# esp32.net
KiCad netlist of a schematic drawn in Altium Designer
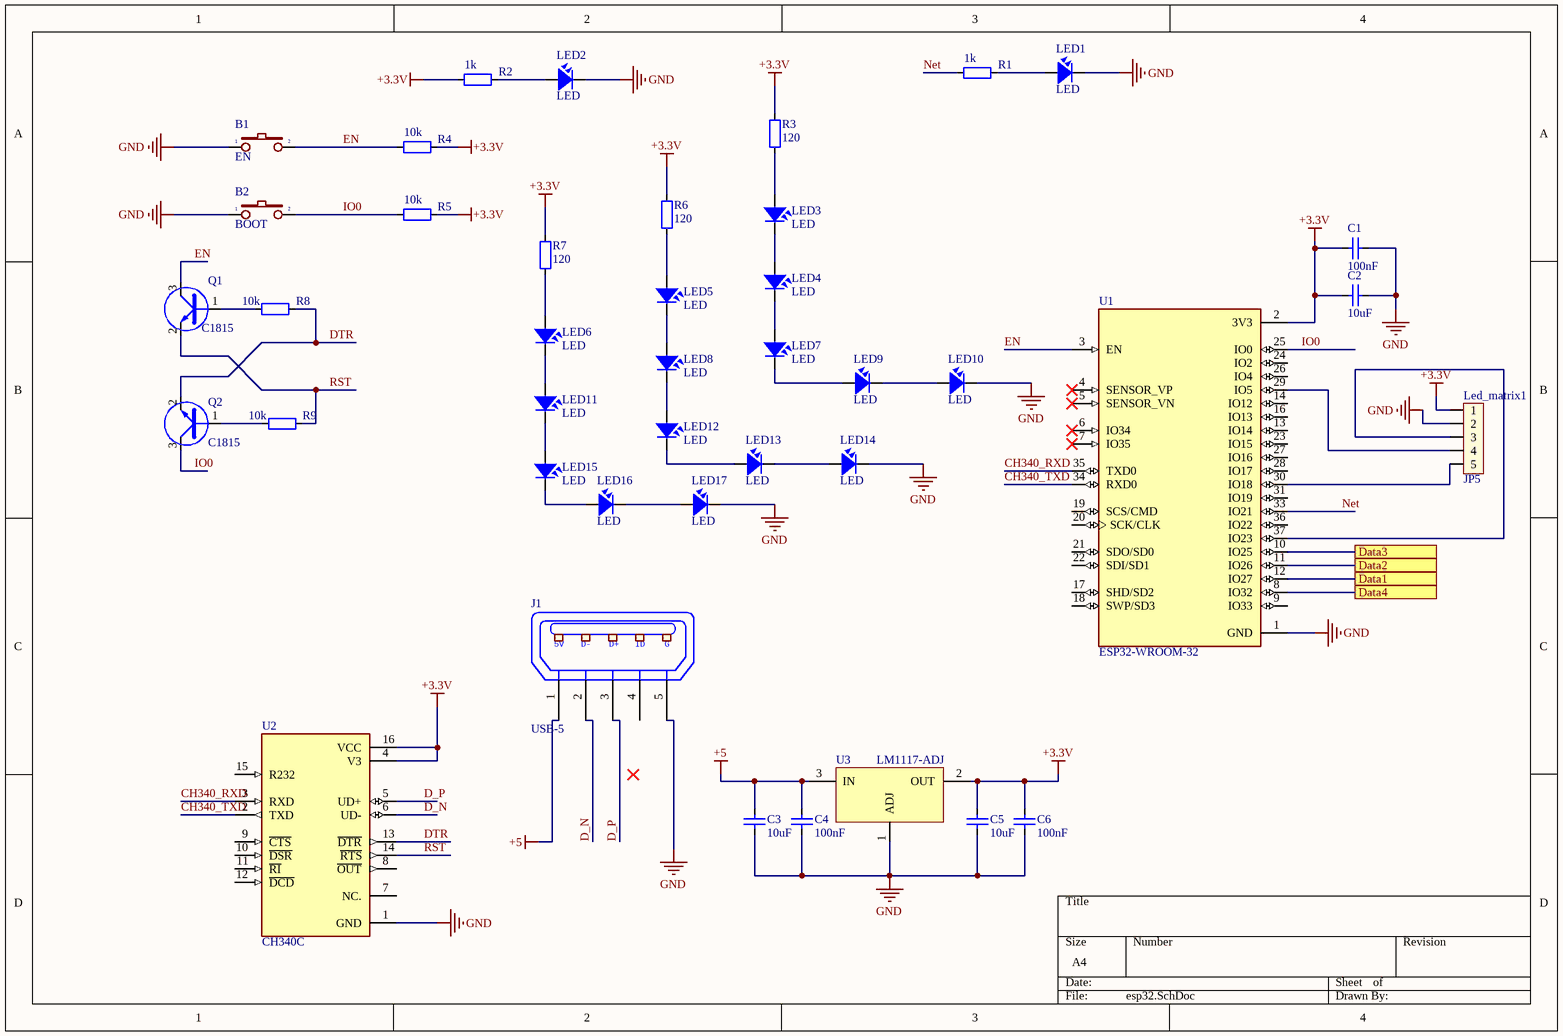
[diagram p0: esp32.SchDoc]

(export (version "E")
  (design (tool "Eeschema 10.0.6"))
  (components
    (comp (ref "B1")
      (value "EN")
      (footprint "BUTTON_2_SMD")
      (libsource (lib "My Library") (part "Button 3x4x2.5"))
    )
    (comp (ref "B2")
      (value "BOOT")
      (footprint "BUTTON_2_SMD")
      (libsource (lib "My Library") (part "Button 3x4x2.5"))
    )
    (comp (ref "C1")
      (value "100nF")
      (footprint "CAP_0805")
      (description "Capacitor")
      (fields (field (name "PUBLISHER") "Altium Limited"))
      (libsource (lib "My Library") (part "CapSMD"))
    )
    (comp (ref "C2")
      (value "10uF")
      (footprint "CAP_0805")
      (description "Capacitor")
      (fields (field (name "PUBLISHER") "Altium Limited"))
      (libsource (lib "My Library") (part "CapSMD"))
    )
    (comp (ref "C3")
      (value "10uF")
      (footprint "CAP_0805")
      (description "Capacitor")
      (fields (field (name "PUBLISHER") "Altium Limited"))
      (libsource (lib "My Library") (part "CapSMD"))
    )
    (comp (ref "C4")
      (value "100nF")
      (footprint "CAP_0805")
      (description "Capacitor")
      (fields (field (name "PUBLISHER") "Altium Limited"))
      (libsource (lib "My Library") (part "CapSMD"))
    )
    (comp (ref "C5")
      (value "10uF")
      (footprint "CAP_0805")
      (description "Capacitor")
      (fields (field (name "PUBLISHER") "Altium Limited"))
      (libsource (lib "My Library") (part "CapSMD"))
    )
    (comp (ref "C6")
      (value "100nF")
      (footprint "CAP_0805")
      (description "Capacitor")
      (fields (field (name "PUBLISHER") "Altium Limited"))
      (libsource (lib "My Library") (part "CapSMD"))
    )
    (comp (ref "J1")
      (value "USB-5")
      (footprint "USB-M1")
      (fields
        (field (name "MANUFACTURER") "FCI")
        (field (name "MANUFACTURER PART NUMBER") "10118193-0001LF")
        (field (name ".CREATOR") "MM")
        (field (name ".CHECKED PCB") "RF")
        (field (name ".CHECKED SCH") "MM")
      )
      (libsource (lib "My Library") (part "USB-5"))
    )
    (comp (ref "LED1")
      (value "LED")
      (footprint "LED-0805-Red")
      (description "LED Single colour Green and Red")
      (libsource (lib "My Library") (part "LED"))
    )
    (comp (ref "LED2")
      (value "LED")
      (footprint "LED-0805-Red")
      (description "LED Single colour Green and Red")
      (libsource (lib "My Library") (part "LED"))
    )
    (comp (ref "LED3")
      (value "LED")
      (footprint "LED-0805-Red")
      (description "LED Single colour Green and Red")
      (libsource (lib "My Library") (part "LED"))
    )
    (comp (ref "LED4")
      (value "LED")
      (footprint "LED-0805-Red")
      (description "LED Single colour Green and Red")
      (libsource (lib "My Library") (part "LED"))
    )
    (comp (ref "LED5")
      (value "LED")
      (footprint "LED-0805-Red")
      (description "LED Single colour Green and Red")
      (libsource (lib "My Library") (part "LED"))
    )
    (comp (ref "LED6")
      (value "LED")
      (footprint "LED-0805-Red")
      (description "LED Single colour Green and Red")
      (libsource (lib "My Library") (part "LED"))
    )
    (comp (ref "LED7")
      (value "LED")
      (footprint "LED-0805-Red")
      (description "LED Single colour Green and Red")
      (libsource (lib "My Library") (part "LED"))
    )
    (comp (ref "LED8")
      (value "LED")
      (footprint "LED-0805-Red")
      (description "LED Single colour Green and Red")
      (libsource (lib "My Library") (part "LED"))
    )
    (comp (ref "LED9")
      (value "LED")
      (footprint "LED-0805-Red")
      (description "LED Single colour Green and Red")
      (libsource (lib "My Library") (part "LED"))
    )
    (comp (ref "LED10")
      (value "LED")
      (footprint "LED-0805-Red")
      (description "LED Single colour Green and Red")
      (libsource (lib "My Library") (part "LED"))
    )
    (comp (ref "LED11")
      (value "LED")
      (footprint "LED-0805-Red")
      (description "LED Single colour Green and Red")
      (libsource (lib "My Library") (part "LED"))
    )
    (comp (ref "LED12")
      (value "LED")
      (footprint "LED-0805-Red")
      (description "LED Single colour Green and Red")
      (libsource (lib "My Library") (part "LED"))
    )
    (comp (ref "LED13")
      (value "LED")
      (footprint "LED-0805-Red")
      (description "LED Single colour Green and Red")
      (libsource (lib "My Library") (part "LED"))
    )
    (comp (ref "LED14")
      (value "LED")
      (footprint "LED-0805-Red")
      (description "LED Single colour Green and Red")
      (libsource (lib "My Library") (part "LED"))
    )
    (comp (ref "LED15")
      (value "LED")
      (footprint "LED-0805-Red")
      (description "LED Single colour Green and Red")
      (libsource (lib "My Library") (part "LED"))
    )
    (comp (ref "LED16")
      (value "LED")
      (footprint "LED-0805-Red")
      (description "LED Single colour Green and Red")
      (libsource (lib "My Library") (part "LED"))
    )
    (comp (ref "LED17")
      (value "LED")
      (footprint "LED-0805-Red")
      (description "LED Single colour Green and Red")
      (libsource (lib "My Library") (part "LED"))
    )
    (comp (ref "Led_matrix1") (value "JP5") (footprint "JP5H") (libsource (lib "My Library") (part "JP5")))
    (comp (ref "Q1")
      (value "C1815")
      (footprint "SOT23")
      (description "NPN 600mW, ECB")
      (libsource (lib "My Library") (part "2SC1815"))
    )
    (comp (ref "Q2")
      (value "C1815")
      (footprint "SOT23")
      (description "NPN 600mW, ECB")
      (libsource (lib "") (part "2SC1815_1"))
    )
    (comp (ref "R1")
      (value "1k")
      (footprint "RES-SMD-0805")
      (description "Resistor")
      (fields
        (field (name "MANUFACTURER") "Generic Components")
        (field (name "PUBLISHER") "Altium Hobart Technology Centre")
      )
      (libsource (lib "My Library") (part "Resistor - SMD"))
    )
    (comp (ref "R2")
      (value "1k")
      (footprint "RES-SMD-0805")
      (description "Resistor")
      (fields
        (field (name "MANUFACTURER") "Generic Components")
        (field (name "PUBLISHER") "Altium Hobart Technology Centre")
      )
      (libsource (lib "My Library") (part "Resistor - SMD"))
    )
    (comp (ref "R3")
      (value "120")
      (footprint "RES-SMD-0805")
      (description "Resistor")
      (fields
        (field (name "MANUFACTURER") "Generic Components")
        (field (name "PUBLISHER") "Altium Hobart Technology Centre")
      )
      (libsource (lib "My Library") (part "Resistor - SMD"))
    )
    (comp (ref "R4")
      (value "10k")
      (footprint "RES-SMD-0805")
      (description "Resistor")
      (fields
        (field (name "MANUFACTURER") "Generic Components")
        (field (name "PUBLISHER") "Altium Hobart Technology Centre")
      )
      (libsource (lib "My Library") (part "Resistor - SMD"))
    )
    (comp (ref "R5")
      (value "10k")
      (footprint "RES-SMD-0805")
      (description "Resistor")
      (fields
        (field (name "MANUFACTURER") "Generic Components")
        (field (name "PUBLISHER") "Altium Hobart Technology Centre")
      )
      (libsource (lib "My Library") (part "Resistor - SMD"))
    )
    (comp (ref "R6")
      (value "120")
      (footprint "RES-SMD-0805")
      (description "Resistor")
      (fields
        (field (name "MANUFACTURER") "Generic Components")
        (field (name "PUBLISHER") "Altium Hobart Technology Centre")
      )
      (libsource (lib "My Library") (part "Resistor - SMD"))
    )
    (comp (ref "R7")
      (value "120")
      (footprint "RES-SMD-0805")
      (description "Resistor")
      (fields
        (field (name "MANUFACTURER") "Generic Components")
        (field (name "PUBLISHER") "Altium Hobart Technology Centre")
      )
      (libsource (lib "My Library") (part "Resistor - SMD"))
    )
    (comp (ref "R8")
      (value "10k")
      (footprint "RES-SMD-0805")
      (description "Resistor")
      (fields
        (field (name "MANUFACTURER") "Generic Components")
        (field (name "PUBLISHER") "Altium Hobart Technology Centre")
      )
      (libsource (lib "My Library") (part "Resistor - SMD"))
    )
    (comp (ref "R9")
      (value "10k")
      (footprint "RES-SMD-0805")
      (description "Resistor")
      (fields
        (field (name "MANUFACTURER") "Generic Components")
        (field (name "PUBLISHER") "Altium Hobart Technology Centre")
      )
      (libsource (lib "My Library") (part "Resistor - SMD"))
    )
    (comp (ref "U1")
      (value "ESP32-WROOM-32")
      (footprint "ESP32_WROOM32E")
      (description "Bluetooth, WiFi Transceiver Module 2.4GHz ~ 2.5GHz Surface Mount")
      (fields (field (name "MF") "Espressif Systems") (field (name "DIGI-KEY_PART_NUMBER") "1904-1010-1-ND"))
      (libsource (lib "My Library") (part "ESP32-WROOM-32"))
    )
    (comp (ref "U2")
      (value "CH340C")
      (footprint "SOIC127P600X180-16N")
      (description "USB to serial chip CH340")
      (fields (field (name "MF") "WCH"))
      (libsource (lib "CH340C") (part "CH340C"))
    )
    (comp (ref "U3")
      (value "LM1117-ADJ")
      (footprint "LM1117-SOP")
      (description "800mA Low-Dropout Linear Regulator")
      (fields (field (name "CREATOR") "Nguyen Ba Bien"))
      (libsource (lib "My Library") (part "LM1117-ADJ"))
    )
  )
  (nets
    (net (code "1") (name "+3.3V") (class "Default")
      (node (ref "C1") (pin "1") (pinfunction "1_1") (pintype "passive"))
      (node (ref "C2") (pin "1") (pinfunction "1_1") (pintype "passive"))
      (node (ref "C5") (pin "1") (pinfunction "1_1") (pintype "passive"))
      (node (ref "C6") (pin "1") (pinfunction "1_1") (pintype "passive"))
      (node (ref "Led_matrix1") (pin "1") (pinfunction "1_1") (pintype "passive"))
      (node (ref "R2") (pin "2") (pinfunction "2_2") (pintype "passive"))
      (node (ref "R3") (pin "1") (pinfunction "1_1") (pintype "passive"))
      (node (ref "R4") (pin "1") (pinfunction "1_1") (pintype "passive"))
      (node (ref "R5") (pin "1") (pinfunction "1_1") (pintype "passive"))
      (node (ref "R6") (pin "1") (pinfunction "1_1") (pintype "passive"))
      (node (ref "R7") (pin "1") (pinfunction "1_1") (pintype "passive"))
      (node (ref "U1") (pin "2") (pinfunction "3V3_2") (pintype "power_in"))
      (node (ref "U2") (pin "16") (pinfunction "VCC_16") (pintype "power_in"))
      (node (ref "U2") (pin "4") (pinfunction "V3_4") (pintype "power_in"))
      (node (ref "U3") (pin "2") (pinfunction "OUT_2") (pintype "passive"))
    )
    (net (code "2") (name "+5") (class "Default")
      (node (ref "C3") (pin "1") (pinfunction "1_1") (pintype "passive"))
      (node (ref "C4") (pin "1") (pinfunction "1_1") (pintype "passive"))
      (node (ref "J1") (pin "1") (pinfunction "P1_1") (pintype "passive"))
      (node (ref "U3") (pin "3") (pinfunction "IN_3") (pintype "passive"))
    )
    (net (code "3") (name "/CH340_RXD") (class "Default")
      (node (ref "U1") (pin "35") (pinfunction "TXD0_35") (pintype "bidirectional"))
      (node (ref "U2") (pin "3") (pinfunction "RXD_3") (pintype "input"))
    )
    (net (code "4") (name "/CH340_TXD") (class "Default")
      (node (ref "U1") (pin "34") (pinfunction "RXD0_34") (pintype "bidirectional"))
      (node (ref "U2") (pin "2") (pinfunction "TXD_2") (pintype "output"))
    )
    (net (code "5") (name "/DTR") (class "Default")
      (node (ref "Q2") (pin "2") (pinfunction "E_2") (pintype "passive"))
      (node (ref "R8") (pin "1") (pinfunction "1_1") (pintype "passive"))
      (node (ref "U2") (pin "13") (pinfunction "~{DTR}_13") (pintype "output"))
    )
    (net (code "6") (name "/D_N") (class "Default")
      (node (ref "J1") (pin "2") (pinfunction "P2_2") (pintype "passive"))
      (node (ref "U2") (pin "6") (pinfunction "UD-_6") (pintype "bidirectional"))
    )
    (net (code "7") (name "/D_P") (class "Default")
      (node (ref "J1") (pin "3") (pinfunction "P3_3") (pintype "passive"))
      (node (ref "U2") (pin "5") (pinfunction "UD+_5") (pintype "bidirectional"))
    )
    (net (code "8") (name "/Data1") (class "Default")
      (node (ref "U1") (pin "12") (pinfunction "IO27_12") (pintype "bidirectional"))
    )
    (net (code "9") (name "/Data2") (class "Default")
      (node (ref "U1") (pin "11") (pinfunction "IO26_11") (pintype "bidirectional"))
    )
    (net (code "10") (name "/Data3") (class "Default")
      (node (ref "U1") (pin "10") (pinfunction "IO25_10") (pintype "bidirectional"))
    )
    (net (code "11") (name "/Data4") (class "Default")
      (node (ref "U1") (pin "8") (pinfunction "IO32_8") (pintype "bidirectional"))
    )
    (net (code "12") (name "/EN") (class "Default")
      (node (ref "B1") (pin "2") (pinfunction "2_2") (pintype "passive"))
      (node (ref "Q1") (pin "3") (pinfunction "C_3") (pintype "passive"))
      (node (ref "R4") (pin "2") (pinfunction "2_2") (pintype "passive"))
      (node (ref "U1") (pin "3") (pinfunction "EN_3") (pintype "input"))
    )
    (net (code "13") (name "/IO0") (class "Default")
      (node (ref "B2") (pin "2") (pinfunction "2_2") (pintype "passive"))
      (node (ref "Q2") (pin "3") (pinfunction "C_3") (pintype "passive"))
      (node (ref "R5") (pin "2") (pinfunction "2_2") (pintype "passive"))
      (node (ref "U1") (pin "25") (pinfunction "IO0_25") (pintype "bidirectional"))
    )
    (net (code "14") (name "/Net") (class "Default")
      (node (ref "R1") (pin "2") (pinfunction "2_2") (pintype "passive"))
      (node (ref "U1") (pin "33") (pinfunction "IO21_33") (pintype "bidirectional"))
    )
    (net (code "15") (name "/RST") (class "Default")
      (node (ref "Q1") (pin "2") (pinfunction "E_2") (pintype "passive"))
      (node (ref "R9") (pin "1") (pinfunction "1_1") (pintype "passive"))
      (node (ref "U2") (pin "14") (pinfunction "~{RTS}_14") (pintype "output"))
    )
    (net (code "16") (name "GND") (class "Default")
      (node (ref "B1") (pin "1") (pinfunction "1_1") (pintype "passive"))
      (node (ref "B2") (pin "1") (pinfunction "1_1") (pintype "passive"))
      (node (ref "C1") (pin "2") (pinfunction "2_2") (pintype "passive"))
      (node (ref "C2") (pin "2") (pinfunction "2_2") (pintype "passive"))
      (node (ref "C3") (pin "2") (pinfunction "2_2") (pintype "passive"))
      (node (ref "C4") (pin "2") (pinfunction "2_2") (pintype "passive"))
      (node (ref "C5") (pin "2") (pinfunction "2_2") (pintype "passive"))
      (node (ref "C6") (pin "2") (pinfunction "2_2") (pintype "passive"))
      (node (ref "J1") (pin "5") (pinfunction "P5_5") (pintype "passive"))
      (node (ref "LED1") (pin "2") (pinfunction "2_2") (pintype "passive"))
      (node (ref "LED10") (pin "2") (pinfunction "2_2") (pintype "passive"))
      (node (ref "LED14") (pin "2") (pinfunction "2_2") (pintype "passive"))
      (node (ref "LED17") (pin "2") (pinfunction "2_2") (pintype "passive"))
      (node (ref "LED2") (pin "2") (pinfunction "2_2") (pintype "passive"))
      (node (ref "Led_matrix1") (pin "2") (pinfunction "2_2") (pintype "passive"))
      (node (ref "U1") (pin "1") (pinfunction "GND_1") (pintype "power_in"))
      (node (ref "U2") (pin "1") (pinfunction "GND_1") (pintype "power_in"))
      (node (ref "U3") (pin "1") (pinfunction "ADJ_1") (pintype "passive"))
    )
    (net (code "17") (name "Net-(LED1-Pad1)") (class "Default")
      (node (ref "LED1") (pin "1") (pinfunction "1_1") (pintype "passive"))
      (node (ref "R1") (pin "1") (pinfunction "1_1") (pintype "passive"))
    )
    (net (code "18") (name "Net-(LED2-Pad1)") (class "Default")
      (node (ref "LED2") (pin "1") (pinfunction "1_1") (pintype "passive"))
      (node (ref "R2") (pin "1") (pinfunction "1_1") (pintype "passive"))
    )
    (net (code "19") (name "Net-(LED3-Pad1)") (class "Default")
      (node (ref "LED3") (pin "1") (pinfunction "1_1") (pintype "passive"))
      (node (ref "R3") (pin "2") (pinfunction "2_2") (pintype "passive"))
    )
    (net (code "20") (name "Net-(LED3-Pad2)") (class "Default")
      (node (ref "LED3") (pin "2") (pinfunction "2_2") (pintype "passive"))
      (node (ref "LED4") (pin "1") (pinfunction "1_1") (pintype "passive"))
    )
    (net (code "21") (name "Net-(LED4-Pad2)") (class "Default")
      (node (ref "LED4") (pin "2") (pinfunction "2_2") (pintype "passive"))
      (node (ref "LED7") (pin "1") (pinfunction "1_1") (pintype "passive"))
    )
    (net (code "22") (name "Net-(LED5-Pad1)") (class "Default")
      (node (ref "LED5") (pin "1") (pinfunction "1_1") (pintype "passive"))
      (node (ref "R6") (pin "2") (pinfunction "2_2") (pintype "passive"))
    )
    (net (code "23") (name "Net-(LED5-Pad2)") (class "Default")
      (node (ref "LED5") (pin "2") (pinfunction "2_2") (pintype "passive"))
      (node (ref "LED8") (pin "1") (pinfunction "1_1") (pintype "passive"))
    )
    (net (code "24") (name "Net-(LED6-Pad1)") (class "Default")
      (node (ref "LED6") (pin "1") (pinfunction "1_1") (pintype "passive"))
      (node (ref "R7") (pin "2") (pinfunction "2_2") (pintype "passive"))
    )
    (net (code "25") (name "Net-(LED7-Pad2)") (class "Default")
      (node (ref "LED7") (pin "2") (pinfunction "2_2") (pintype "passive"))
      (node (ref "LED9") (pin "1") (pinfunction "1_1") (pintype "passive"))
    )
    (net (code "26") (name "Net-(LED10-Pad1)") (class "Default")
      (node (ref "LED10") (pin "1") (pinfunction "1_1") (pintype "passive"))
      (node (ref "LED9") (pin "2") (pinfunction "2_2") (pintype "passive"))
    )
    (net (code "27") (name "Net-(LED11-Pad1)") (class "Default")
      (node (ref "LED11") (pin "1") (pinfunction "1_1") (pintype "passive"))
      (node (ref "LED6") (pin "2") (pinfunction "2_2") (pintype "passive"))
    )
    (net (code "28") (name "Net-(LED11-Pad2)") (class "Default")
      (node (ref "LED11") (pin "2") (pinfunction "2_2") (pintype "passive"))
      (node (ref "LED15") (pin "1") (pinfunction "1_1") (pintype "passive"))
    )
    (net (code "29") (name "Net-(LED12-Pad1)") (class "Default")
      (node (ref "LED12") (pin "1") (pinfunction "1_1") (pintype "passive"))
      (node (ref "LED8") (pin "2") (pinfunction "2_2") (pintype "passive"))
    )
    (net (code "30") (name "Net-(LED12-Pad2)") (class "Default")
      (node (ref "LED12") (pin "2") (pinfunction "2_2") (pintype "passive"))
      (node (ref "LED13") (pin "1") (pinfunction "1_1") (pintype "passive"))
    )
    (net (code "31") (name "Net-(LED13-Pad2)") (class "Default")
      (node (ref "LED13") (pin "2") (pinfunction "2_2") (pintype "passive"))
      (node (ref "LED14") (pin "1") (pinfunction "1_1") (pintype "passive"))
    )
    (net (code "32") (name "Net-(LED15-Pad2)") (class "Default")
      (node (ref "LED15") (pin "2") (pinfunction "2_2") (pintype "passive"))
      (node (ref "LED16") (pin "1") (pinfunction "1_1") (pintype "passive"))
    )
    (net (code "33") (name "Net-(LED16-Pad2)") (class "Default")
      (node (ref "LED16") (pin "2") (pinfunction "2_2") (pintype "passive"))
      (node (ref "LED17") (pin "1") (pinfunction "1_1") (pintype "passive"))
    )
    (net (code "34") (name "Net-(Q1-B)") (class "Default")
      (node (ref "Q1") (pin "1") (pinfunction "B_1") (pintype "passive"))
      (node (ref "R8") (pin "2") (pinfunction "2_2") (pintype "passive"))
    )
    (net (code "35") (name "Net-(Q2-B)") (class "Default")
      (node (ref "Q2") (pin "1") (pinfunction "B_1") (pintype "passive"))
      (node (ref "R9") (pin "2") (pinfunction "2_2") (pintype "passive"))
    )
    (net (code "36") (name "Net-(U1-IO5)") (class "Default")
      (node (ref "Led_matrix1") (pin "4") (pinfunction "4_4") (pintype "passive"))
      (node (ref "U1") (pin "29") (pinfunction "IO5_29") (pintype "bidirectional"))
    )
    (net (code "37") (name "Net-(U1-IO18)") (class "Default")
      (node (ref "Led_matrix1") (pin "5") (pinfunction "5_5") (pintype "passive"))
      (node (ref "U1") (pin "30") (pinfunction "IO18_30") (pintype "bidirectional"))
    )
    (net (code "38") (name "Net-(U1-IO23)") (class "Default")
      (node (ref "Led_matrix1") (pin "3") (pinfunction "3_3") (pintype "passive"))
      (node (ref "U1") (pin "37") (pinfunction "IO23_37") (pintype "bidirectional"))
    )
    (net (code "39") (name "unconnected-(J1-P4-Pad4)") (class "Default")
      (node (ref "J1") (pin "4") (pinfunction "P4_4") (pintype "passive"))
    )
    (net (code "40") (name "unconnected-(U1-IO2-Pad24)") (class "Default")
      (node (ref "U1") (pin "24") (pinfunction "IO2_24") (pintype "bidirectional"))
    )
    (net (code "41") (name "unconnected-(U1-IO4-Pad26)") (class "Default")
      (node (ref "U1") (pin "26") (pinfunction "IO4_26") (pintype "bidirectional"))
    )
    (net (code "42") (name "unconnected-(U1-IO12-Pad14)") (class "Default")
      (node (ref "U1") (pin "14") (pinfunction "IO12_14") (pintype "bidirectional"))
    )
    (net (code "43") (name "unconnected-(U1-IO13-Pad16)") (class "Default")
      (node (ref "U1") (pin "16") (pinfunction "IO13_16") (pintype "bidirectional"))
    )
    (net (code "44") (name "unconnected-(U1-IO14-Pad13)") (class "Default")
      (node (ref "U1") (pin "13") (pinfunction "IO14_13") (pintype "bidirectional"))
    )
    (net (code "45") (name "unconnected-(U1-IO15-Pad23)") (class "Default")
      (node (ref "U1") (pin "23") (pinfunction "IO15_23") (pintype "bidirectional"))
    )
    (net (code "46") (name "unconnected-(U1-IO16-Pad27)") (class "Default")
      (node (ref "U1") (pin "27") (pinfunction "IO16_27") (pintype "bidirectional"))
    )
    (net (code "47") (name "unconnected-(U1-IO17-Pad28)") (class "Default")
      (node (ref "U1") (pin "28") (pinfunction "IO17_28") (pintype "bidirectional"))
    )
    (net (code "48") (name "unconnected-(U1-IO19-Pad31)") (class "Default")
      (node (ref "U1") (pin "31") (pinfunction "IO19_31") (pintype "bidirectional"))
    )
    (net (code "49") (name "unconnected-(U1-IO22-Pad36)") (class "Default")
      (node (ref "U1") (pin "36") (pinfunction "IO22_36") (pintype "bidirectional"))
    )
    (net (code "50") (name "unconnected-(U1-IO33-Pad9)") (class "Default")
      (node (ref "U1") (pin "9") (pinfunction "IO33_9") (pintype "bidirectional"))
    )
    (net (code "51") (name "unconnected-(U1-IO34-Pad6)") (class "Default")
      (node (ref "U1") (pin "6") (pinfunction "IO34_6") (pintype "input+no_connect"))
    )
    (net (code "52") (name "unconnected-(U1-IO35-Pad7)") (class "Default")
      (node (ref "U1") (pin "7") (pinfunction "IO35_7") (pintype "input+no_connect"))
    )
    (net (code "53") (name "unconnected-(U1-SCK{slash}CLK-Pad20)") (class "Default")
      (node (ref "U1") (pin "20") (pinfunction "SCK/CLK_20") (pintype "bidirectional"))
    )
    (net (code "54") (name "unconnected-(U1-SCS{slash}CMD-Pad19)") (class "Default")
      (node (ref "U1") (pin "19") (pinfunction "SCS/CMD_19") (pintype "bidirectional"))
    )
    (net (code "55") (name "unconnected-(U1-SDI{slash}SD1-Pad22)") (class "Default")
      (node (ref "U1") (pin "22") (pinfunction "SDI/SD1_22") (pintype "bidirectional"))
    )
    (net (code "56") (name "unconnected-(U1-SDO{slash}SD0-Pad21)") (class "Default")
      (node (ref "U1") (pin "21") (pinfunction "SDO/SD0_21") (pintype "bidirectional"))
    )
    (net (code "57") (name "unconnected-(U1-SENSOR_VN-Pad5)") (class "Default")
      (node (ref "U1") (pin "5") (pinfunction "SENSOR_VN_5") (pintype "input+no_connect"))
    )
    (net (code "58") (name "unconnected-(U1-SENSOR_VP-Pad4)") (class "Default")
      (node (ref "U1") (pin "4") (pinfunction "SENSOR_VP_4") (pintype "input+no_connect"))
    )
    (net (code "59") (name "unconnected-(U1-SHD{slash}SD2-Pad17)") (class "Default")
      (node (ref "U1") (pin "17") (pinfunction "SHD/SD2_17") (pintype "bidirectional"))
    )
    (net (code "60") (name "unconnected-(U1-SWP{slash}SD3-Pad18)") (class "Default")
      (node (ref "U1") (pin "18") (pinfunction "SWP/SD3_18") (pintype "bidirectional"))
    )
    (net (code "61") (name "unconnected-(U2-NC.-Pad7)") (class "Default")
      (node (ref "U2") (pin "7") (pinfunction "NC._7") (pintype "passive"))
    )
    (net (code "62") (name "unconnected-(U2-R232-Pad15)") (class "Default")
      (node (ref "U2") (pin "15") (pinfunction "R232_15") (pintype "input"))
    )
    (net (code "63") (name "unconnected-(U2-~{CTS}-Pad9)") (class "Default")
      (node (ref "U2") (pin "9") (pinfunction "~{CTS}_9") (pintype "input"))
    )
    (net (code "64") (name "unconnected-(U2-~{DCD}-Pad12)") (class "Default")
      (node (ref "U2") (pin "12") (pinfunction "~{DCD}_12") (pintype "input"))
    )
    (net (code "65") (name "unconnected-(U2-~{DSR}-Pad10)") (class "Default")
      (node (ref "U2") (pin "10") (pinfunction "~{DSR}_10") (pintype "input"))
    )
    (net (code "66") (name "unconnected-(U2-~{OUT}-Pad8)") (class "Default")
      (node (ref "U2") (pin "8") (pinfunction "~{OUT}_8") (pintype "output"))
    )
    (net (code "67") (name "unconnected-(U2-~{RI}-Pad11)") (class "Default")
      (node (ref "U2") (pin "11") (pinfunction "~{RI}_11") (pintype "input"))
    )
  )
)
